# LevelConverter.net
KiCad netlist of a schematic drawn in EAGLE
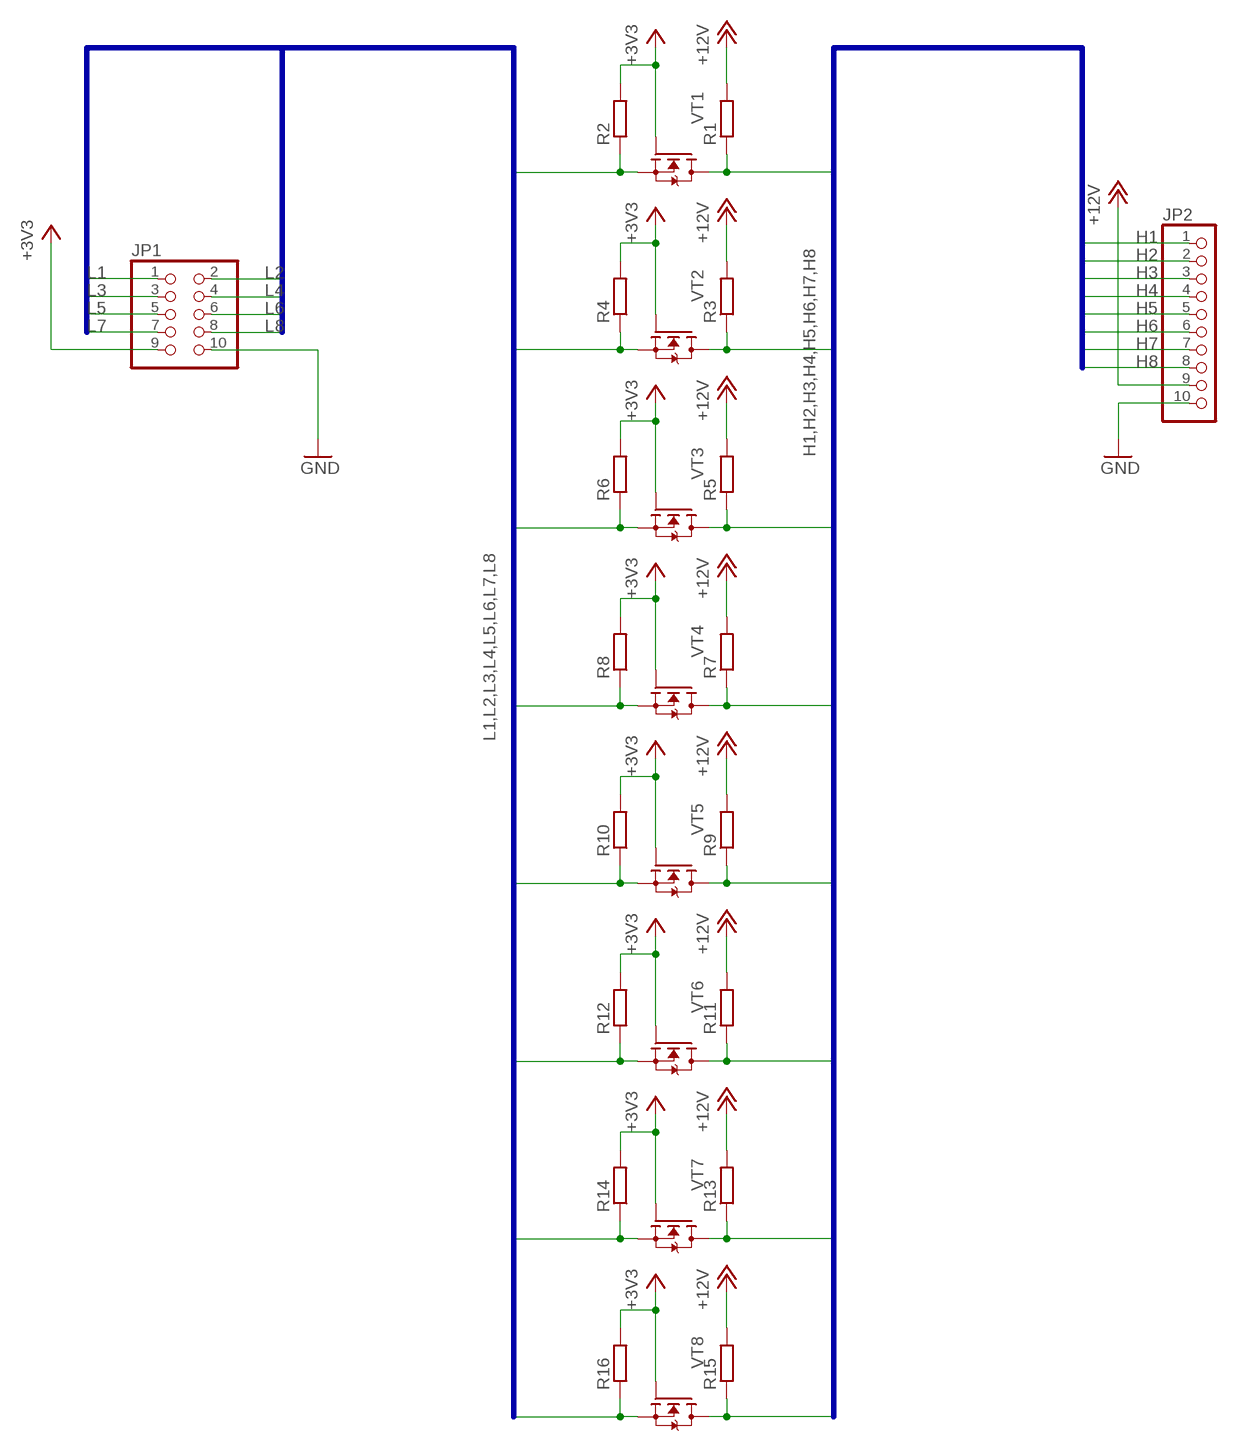
[diagram p0: schematic, sheet 1]

(export (version "E")
  (design (tool "Eeschema 10.0.6"))
  (components
    (comp (ref "JP1")
      (value "PINHD-2X5/90")
      (footprint "eagle-import:2X05_90")
      (libsource (lib "eagle-import") (part "PINHD-2X5/90"))
    )
    (comp (ref "JP2")
      (value "PINHD-1X10")
      (footprint "eagle-import:1X10")
      (libsource (lib "eagle-import") (part "PINHD-1X10"))
    )
    (comp (ref "R1")
      (value "R_R0805")
      (footprint "eagle-import:RESC2012X50")
      (libsource (lib "eagle-import") (part "R_R0805"))
    )
    (comp (ref "R2")
      (value "R_R0805")
      (footprint "eagle-import:RESC2012X50")
      (libsource (lib "eagle-import") (part "R_R0805"))
    )
    (comp (ref "R3")
      (value "R_R0805")
      (footprint "eagle-import:RESC2012X50")
      (libsource (lib "eagle-import") (part "R_R0805"))
    )
    (comp (ref "R4")
      (value "R_R0805")
      (footprint "eagle-import:RESC2012X50")
      (libsource (lib "eagle-import") (part "R_R0805"))
    )
    (comp (ref "R5")
      (value "R_R0805")
      (footprint "eagle-import:RESC2012X50")
      (libsource (lib "eagle-import") (part "R_R0805"))
    )
    (comp (ref "R6")
      (value "R_R0805")
      (footprint "eagle-import:RESC2012X50")
      (libsource (lib "eagle-import") (part "R_R0805"))
    )
    (comp (ref "R7")
      (value "R_R0805")
      (footprint "eagle-import:RESC2012X50")
      (libsource (lib "eagle-import") (part "R_R0805"))
    )
    (comp (ref "R8")
      (value "R_R0805")
      (footprint "eagle-import:RESC2012X50")
      (libsource (lib "eagle-import") (part "R_R0805"))
    )
    (comp (ref "R9")
      (value "R_R0805")
      (footprint "eagle-import:RESC2012X50")
      (libsource (lib "eagle-import") (part "R_R0805"))
    )
    (comp (ref "R10")
      (value "R_R0805")
      (footprint "eagle-import:RESC2012X50")
      (libsource (lib "eagle-import") (part "R_R0805"))
    )
    (comp (ref "R11")
      (value "R_R0805")
      (footprint "eagle-import:RESC2012X50")
      (libsource (lib "eagle-import") (part "R_R0805"))
    )
    (comp (ref "R12")
      (value "R_R0805")
      (footprint "eagle-import:RESC2012X50")
      (libsource (lib "eagle-import") (part "R_R0805"))
    )
    (comp (ref "R13")
      (value "R_R0805")
      (footprint "eagle-import:RESC2012X50")
      (libsource (lib "eagle-import") (part "R_R0805"))
    )
    (comp (ref "R14")
      (value "R_R0805")
      (footprint "eagle-import:RESC2012X50")
      (libsource (lib "eagle-import") (part "R_R0805"))
    )
    (comp (ref "R15")
      (value "R_R0805")
      (footprint "eagle-import:RESC2012X50")
      (libsource (lib "eagle-import") (part "R_R0805"))
    )
    (comp (ref "R16")
      (value "R_R0805")
      (footprint "eagle-import:RESC2012X50")
      (libsource (lib "eagle-import") (part "R_R0805"))
    )
    (comp (ref "VT1")
      (value "FET-NSOT-23")
      (footprint "eagle-import:SOT95P240X115-3")
      (libsource (lib "eagle-import") (part "FET-NSOT-23"))
    )
    (comp (ref "VT2")
      (value "FET-NSOT-23")
      (footprint "eagle-import:SOT95P240X115-3")
      (libsource (lib "eagle-import") (part "FET-NSOT-23"))
    )
    (comp (ref "VT3")
      (value "FET-NSOT-23")
      (footprint "eagle-import:SOT95P240X115-3")
      (libsource (lib "eagle-import") (part "FET-NSOT-23"))
    )
    (comp (ref "VT4")
      (value "FET-NSOT-23")
      (footprint "eagle-import:SOT95P240X115-3")
      (libsource (lib "eagle-import") (part "FET-NSOT-23"))
    )
    (comp (ref "VT5")
      (value "FET-NSOT-23")
      (footprint "eagle-import:SOT95P240X115-3")
      (libsource (lib "eagle-import") (part "FET-NSOT-23"))
    )
    (comp (ref "VT6")
      (value "FET-NSOT-23")
      (footprint "eagle-import:SOT95P240X115-3")
      (libsource (lib "eagle-import") (part "FET-NSOT-23"))
    )
    (comp (ref "VT7")
      (value "FET-NSOT-23")
      (footprint "eagle-import:SOT95P240X115-3")
      (libsource (lib "eagle-import") (part "FET-NSOT-23"))
    )
    (comp (ref "VT8")
      (value "FET-NSOT-23")
      (footprint "eagle-import:SOT95P240X115-3")
      (libsource (lib "eagle-import") (part "FET-NSOT-23"))
    )
  )
  (nets
    (net (code "1") (name "+3V3") (class "Default")
      (node (ref "JP1") (pin "9") (pinfunction "9_9") (pintype "passive"))
      (node (ref "R10") (pin "2") (pinfunction "2_2") (pintype "passive"))
      (node (ref "R12") (pin "2") (pinfunction "2_2") (pintype "passive"))
      (node (ref "R14") (pin "2") (pinfunction "2_2") (pintype "passive"))
      (node (ref "R16") (pin "2") (pinfunction "2_2") (pintype "passive"))
      (node (ref "R2") (pin "2") (pinfunction "2_2") (pintype "passive"))
      (node (ref "R4") (pin "2") (pinfunction "2_2") (pintype "passive"))
      (node (ref "R6") (pin "2") (pinfunction "2_2") (pintype "passive"))
      (node (ref "R8") (pin "2") (pinfunction "2_2") (pintype "passive"))
      (node (ref "VT1") (pin "1") (pinfunction "G_1") (pintype "passive"))
      (node (ref "VT2") (pin "1") (pinfunction "G_1") (pintype "passive"))
      (node (ref "VT3") (pin "1") (pinfunction "G_1") (pintype "passive"))
      (node (ref "VT4") (pin "1") (pinfunction "G_1") (pintype "passive"))
      (node (ref "VT5") (pin "1") (pinfunction "G_1") (pintype "passive"))
      (node (ref "VT6") (pin "1") (pinfunction "G_1") (pintype "passive"))
      (node (ref "VT7") (pin "1") (pinfunction "G_1") (pintype "passive"))
      (node (ref "VT8") (pin "1") (pinfunction "G_1") (pintype "passive"))
    )
    (net (code "2") (name "+12V") (class "Default")
      (node (ref "JP2") (pin "9") (pinfunction "9_9") (pintype "passive"))
      (node (ref "R1") (pin "2") (pinfunction "2_2") (pintype "passive"))
      (node (ref "R11") (pin "2") (pinfunction "2_2") (pintype "passive"))
      (node (ref "R13") (pin "2") (pinfunction "2_2") (pintype "passive"))
      (node (ref "R15") (pin "2") (pinfunction "2_2") (pintype "passive"))
      (node (ref "R3") (pin "2") (pinfunction "2_2") (pintype "passive"))
      (node (ref "R5") (pin "2") (pinfunction "2_2") (pintype "passive"))
      (node (ref "R7") (pin "2") (pinfunction "2_2") (pintype "passive"))
      (node (ref "R9") (pin "2") (pinfunction "2_2") (pintype "passive"))
    )
    (net (code "3") (name "/H1") (class "Default")
      (node (ref "JP2") (pin "1") (pinfunction "1_1") (pintype "passive"))
      (node (ref "R1") (pin "1") (pinfunction "1_1") (pintype "passive"))
      (node (ref "VT1") (pin "3") (pinfunction "D_3") (pintype "passive"))
    )
    (net (code "4") (name "/H2") (class "Default")
      (node (ref "JP2") (pin "2") (pinfunction "2_2") (pintype "passive"))
      (node (ref "R3") (pin "1") (pinfunction "1_1") (pintype "passive"))
      (node (ref "VT2") (pin "3") (pinfunction "D_3") (pintype "passive"))
    )
    (net (code "5") (name "/H3") (class "Default")
      (node (ref "JP2") (pin "3") (pinfunction "3_3") (pintype "passive"))
      (node (ref "R5") (pin "1") (pinfunction "1_1") (pintype "passive"))
      (node (ref "VT3") (pin "3") (pinfunction "D_3") (pintype "passive"))
    )
    (net (code "6") (name "/H4") (class "Default")
      (node (ref "JP2") (pin "4") (pinfunction "4_4") (pintype "passive"))
      (node (ref "R7") (pin "1") (pinfunction "1_1") (pintype "passive"))
      (node (ref "VT4") (pin "3") (pinfunction "D_3") (pintype "passive"))
    )
    (net (code "7") (name "/H5") (class "Default")
      (node (ref "JP2") (pin "5") (pinfunction "5_5") (pintype "passive"))
      (node (ref "R9") (pin "1") (pinfunction "1_1") (pintype "passive"))
      (node (ref "VT5") (pin "3") (pinfunction "D_3") (pintype "passive"))
    )
    (net (code "8") (name "/H6") (class "Default")
      (node (ref "JP2") (pin "6") (pinfunction "6_6") (pintype "passive"))
      (node (ref "R11") (pin "1") (pinfunction "1_1") (pintype "passive"))
      (node (ref "VT6") (pin "3") (pinfunction "D_3") (pintype "passive"))
    )
    (net (code "9") (name "/H7") (class "Default")
      (node (ref "JP2") (pin "7") (pinfunction "7_7") (pintype "passive"))
      (node (ref "R13") (pin "1") (pinfunction "1_1") (pintype "passive"))
      (node (ref "VT7") (pin "3") (pinfunction "D_3") (pintype "passive"))
    )
    (net (code "10") (name "/H8") (class "Default")
      (node (ref "JP2") (pin "8") (pinfunction "8_8") (pintype "passive"))
      (node (ref "R15") (pin "1") (pinfunction "1_1") (pintype "passive"))
      (node (ref "VT8") (pin "3") (pinfunction "D_3") (pintype "passive"))
    )
    (net (code "11") (name "/L1") (class "Default")
      (node (ref "JP1") (pin "1") (pinfunction "1_1") (pintype "passive"))
      (node (ref "R2") (pin "1") (pinfunction "1_1") (pintype "passive"))
      (node (ref "VT1") (pin "2") (pinfunction "S_2") (pintype "passive"))
    )
    (net (code "12") (name "/L2") (class "Default")
      (node (ref "JP1") (pin "2") (pinfunction "2_2") (pintype "passive"))
      (node (ref "R4") (pin "1") (pinfunction "1_1") (pintype "passive"))
      (node (ref "VT2") (pin "2") (pinfunction "S_2") (pintype "passive"))
    )
    (net (code "13") (name "/L3") (class "Default")
      (node (ref "JP1") (pin "3") (pinfunction "3_3") (pintype "passive"))
      (node (ref "R6") (pin "1") (pinfunction "1_1") (pintype "passive"))
      (node (ref "VT3") (pin "2") (pinfunction "S_2") (pintype "passive"))
    )
    (net (code "14") (name "/L4") (class "Default")
      (node (ref "JP1") (pin "4") (pinfunction "4_4") (pintype "passive"))
      (node (ref "R8") (pin "1") (pinfunction "1_1") (pintype "passive"))
      (node (ref "VT4") (pin "2") (pinfunction "S_2") (pintype "passive"))
    )
    (net (code "15") (name "/L5") (class "Default")
      (node (ref "JP1") (pin "5") (pinfunction "5_5") (pintype "passive"))
      (node (ref "R10") (pin "1") (pinfunction "1_1") (pintype "passive"))
      (node (ref "VT5") (pin "2") (pinfunction "S_2") (pintype "passive"))
    )
    (net (code "16") (name "/L6") (class "Default")
      (node (ref "JP1") (pin "6") (pinfunction "6_6") (pintype "passive"))
      (node (ref "R12") (pin "1") (pinfunction "1_1") (pintype "passive"))
      (node (ref "VT6") (pin "2") (pinfunction "S_2") (pintype "passive"))
    )
    (net (code "17") (name "/L7") (class "Default")
      (node (ref "JP1") (pin "7") (pinfunction "7_7") (pintype "passive"))
      (node (ref "R14") (pin "1") (pinfunction "1_1") (pintype "passive"))
      (node (ref "VT7") (pin "2") (pinfunction "S_2") (pintype "passive"))
    )
    (net (code "18") (name "/L8") (class "Default")
      (node (ref "JP1") (pin "8") (pinfunction "8_8") (pintype "passive"))
      (node (ref "R16") (pin "1") (pinfunction "1_1") (pintype "passive"))
      (node (ref "VT8") (pin "2") (pinfunction "S_2") (pintype "passive"))
    )
    (net (code "21") (name "GND") (class "Default")
      (node (ref "JP1") (pin "10") (pinfunction "10_10") (pintype "passive"))
      (node (ref "JP2") (pin "10") (pinfunction "10_10") (pintype "passive"))
    )
  )
)
